# SparkFun_MicroSD_Sniffer.net
KiCad netlist of a schematic drawn in EAGLE
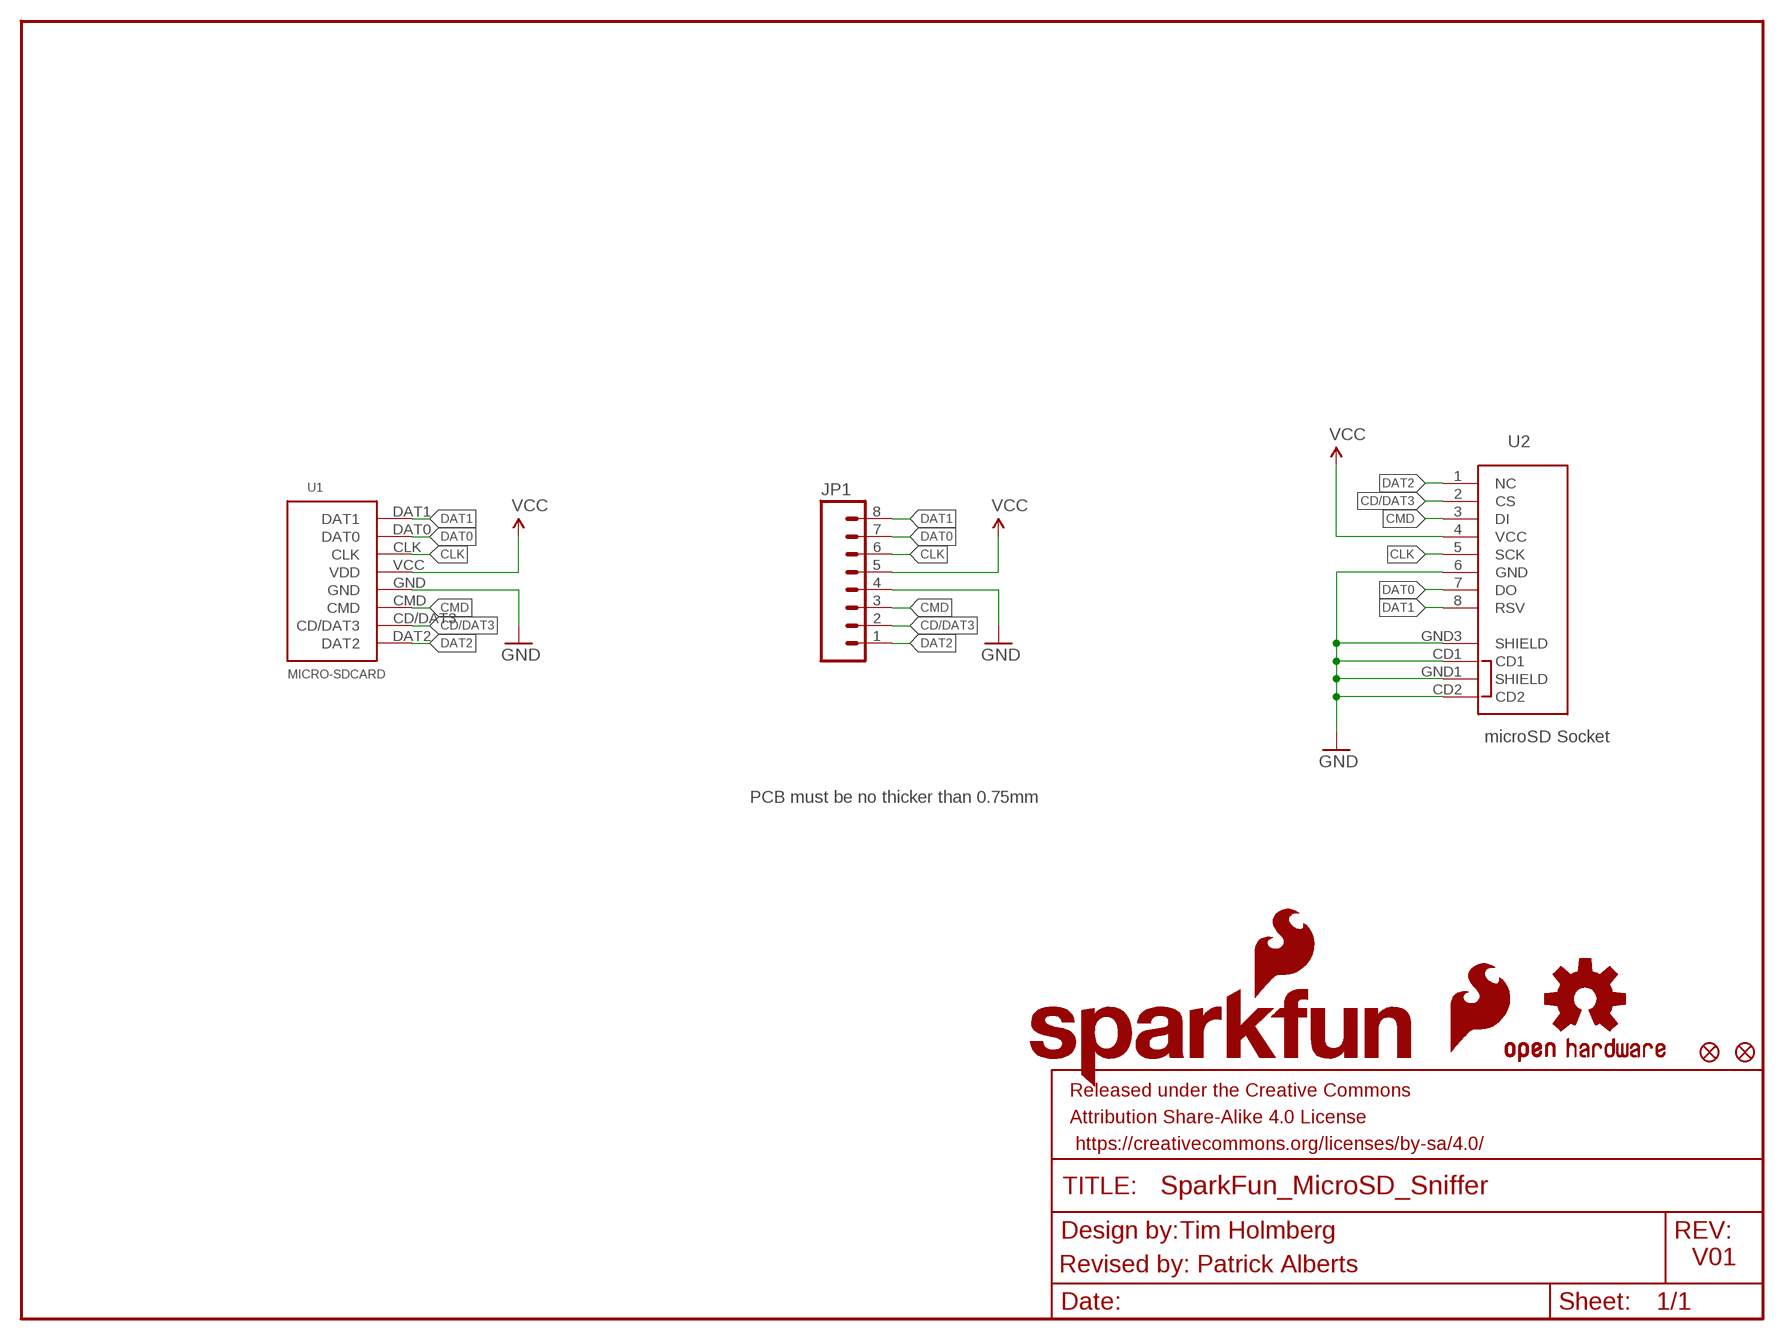
[diagram p0: schematic, sheet 1]

(export (version "E")
  (design (tool "Eeschema 10.0.6"))
  (components
    (comp (ref "FID1")
      (value "FIDUCIAL1X2")
      (footprint "eagle-import:FIDUCIAL-1X2")
      (libsource (lib "eagle-import") (part "FIDUCIAL1X2"))
    )
    (comp (ref "FID2")
      (value "FIDUCIAL1X2")
      (footprint "eagle-import:FIDUCIAL-1X2")
      (libsource (lib "eagle-import") (part "FIDUCIAL1X2"))
    )
    (comp (ref "FRAME1")
      (value "FRAME-LETTER")
      (footprint "eagle-import:CREATIVE_COMMONS")
      (fields (field (name "DESIGNER") "NAME"))
      (libsource (lib "eagle-import") (part "FRAME-LETTER"))
    )
    (comp (ref "JP1")
      (value "M08")
      (footprint "eagle-import:1X08")
      (libsource (lib "eagle-import") (part "M08"))
    )
    (comp (ref "LOGO1")
      (value "OSHW-LOGOM")
      (footprint "eagle-import:OSHW-LOGO-M")
      (libsource (lib "eagle-import") (part "OSHW-LOGOM"))
    )
    (comp (ref "LOGO2")
      (value "SFE_LOGO_FLAME.2_INCH")
      (footprint "eagle-import:SFE_LOGO_FLAME_.2")
      (libsource (lib "eagle-import") (part "SFE_LOGO_FLAME.2_INCH"))
    )
    (comp (ref "LOGO3")
      (value "SFE_LOGO_NAME_FLAME.1_INCH")
      (footprint "eagle-import:SFE_LOGO_NAME_FLAME_.1")
      (libsource (lib "eagle-import") (part "SFE_LOGO_NAME_FLAME.1_INCH"))
    )
    (comp (ref "U1")
      (value "MICRO-SDCARD")
      (footprint "eagle-import:MICRO-SDCARD")
      (libsource (lib "eagle-import") (part "MICRO-SDCARD"))
    )
    (comp (ref "U2")
      (value "microSD Socket")
      (footprint "eagle-import:MICROSD_1_1")
      (libsource (lib "eagle-import") (part "USD-SOCKET"))
    )
  )
  (nets
    (net (code "1") (name "CD{slash}DAT3") (class "Default")
      (node (ref "JP1") (pin "2") (pinfunction "2_2") (pintype "passive"))
      (node (ref "U1") (pin "CD/DAT3") (pinfunction "CD/DAT3_CD/DAT3") (pintype "bidirectional"))
      (node (ref "U2") (pin "2") (pinfunction "CS_2") (pintype "bidirectional"))
    )
    (net (code "2") (name "CLK") (class "Default")
      (node (ref "JP1") (pin "6") (pinfunction "6_6") (pintype "passive"))
      (node (ref "U1") (pin "CLK") (pinfunction "CLK_CLK") (pintype "bidirectional"))
      (node (ref "U2") (pin "5") (pinfunction "SCK_5") (pintype "bidirectional"))
    )
    (net (code "3") (name "CMD") (class "Default")
      (node (ref "JP1") (pin "3") (pinfunction "3_3") (pintype "passive"))
      (node (ref "U1") (pin "CMD") (pinfunction "CMD_CMD") (pintype "bidirectional"))
      (node (ref "U2") (pin "3") (pinfunction "DI_3") (pintype "bidirectional"))
    )
    (net (code "4") (name "DAT0") (class "Default")
      (node (ref "JP1") (pin "7") (pinfunction "7_7") (pintype "passive"))
      (node (ref "U1") (pin "DAT0") (pinfunction "DAT0_DAT0") (pintype "bidirectional"))
      (node (ref "U2") (pin "7") (pinfunction "DO_7") (pintype "bidirectional"))
    )
    (net (code "5") (name "DAT1") (class "Default")
      (node (ref "JP1") (pin "8") (pinfunction "8_8") (pintype "passive"))
      (node (ref "U1") (pin "DAT1") (pinfunction "DAT1_DAT1") (pintype "bidirectional"))
      (node (ref "U2") (pin "8") (pinfunction "RSV_8") (pintype "bidirectional"))
    )
    (net (code "6") (name "DAT2") (class "Default")
      (node (ref "JP1") (pin "1") (pinfunction "1_1") (pintype "passive"))
      (node (ref "U1") (pin "DAT2") (pinfunction "DAT2_DAT2") (pintype "bidirectional"))
      (node (ref "U2") (pin "1") (pinfunction "NC_1") (pintype "bidirectional"))
    )
    (net (code "7") (name "GND") (class "Default")
      (node (ref "JP1") (pin "4") (pinfunction "4_4") (pintype "passive"))
      (node (ref "U1") (pin "GND") (pinfunction "GND_GND") (pintype "bidirectional"))
      (node (ref "U2") (pin "6") (pinfunction "GND_6") (pintype "bidirectional"))
      (node (ref "U2") (pin "CD1") (pinfunction "CD1_CD1") (pintype "bidirectional"))
      (node (ref "U2") (pin "CD2") (pinfunction "CD2_CD2") (pintype "bidirectional"))
      (node (ref "U2") (pin "GND1") (pinfunction "SHIELD_GND1") (pintype "bidirectional"))
      (node (ref "U2") (pin "GND3") (pinfunction "SHIELD_GND3") (pintype "bidirectional"))
    )
    (net (code "8") (name "VCC") (class "Default")
      (node (ref "JP1") (pin "5") (pinfunction "5_5") (pintype "passive"))
      (node (ref "U1") (pin "VCC") (pinfunction "VDD_VCC") (pintype "bidirectional"))
      (node (ref "U2") (pin "4") (pinfunction "VCC_4") (pintype "bidirectional"))
    )
  )
)
